# mainbd.net
KiCad netlist of a schematic drawn in EAGLE
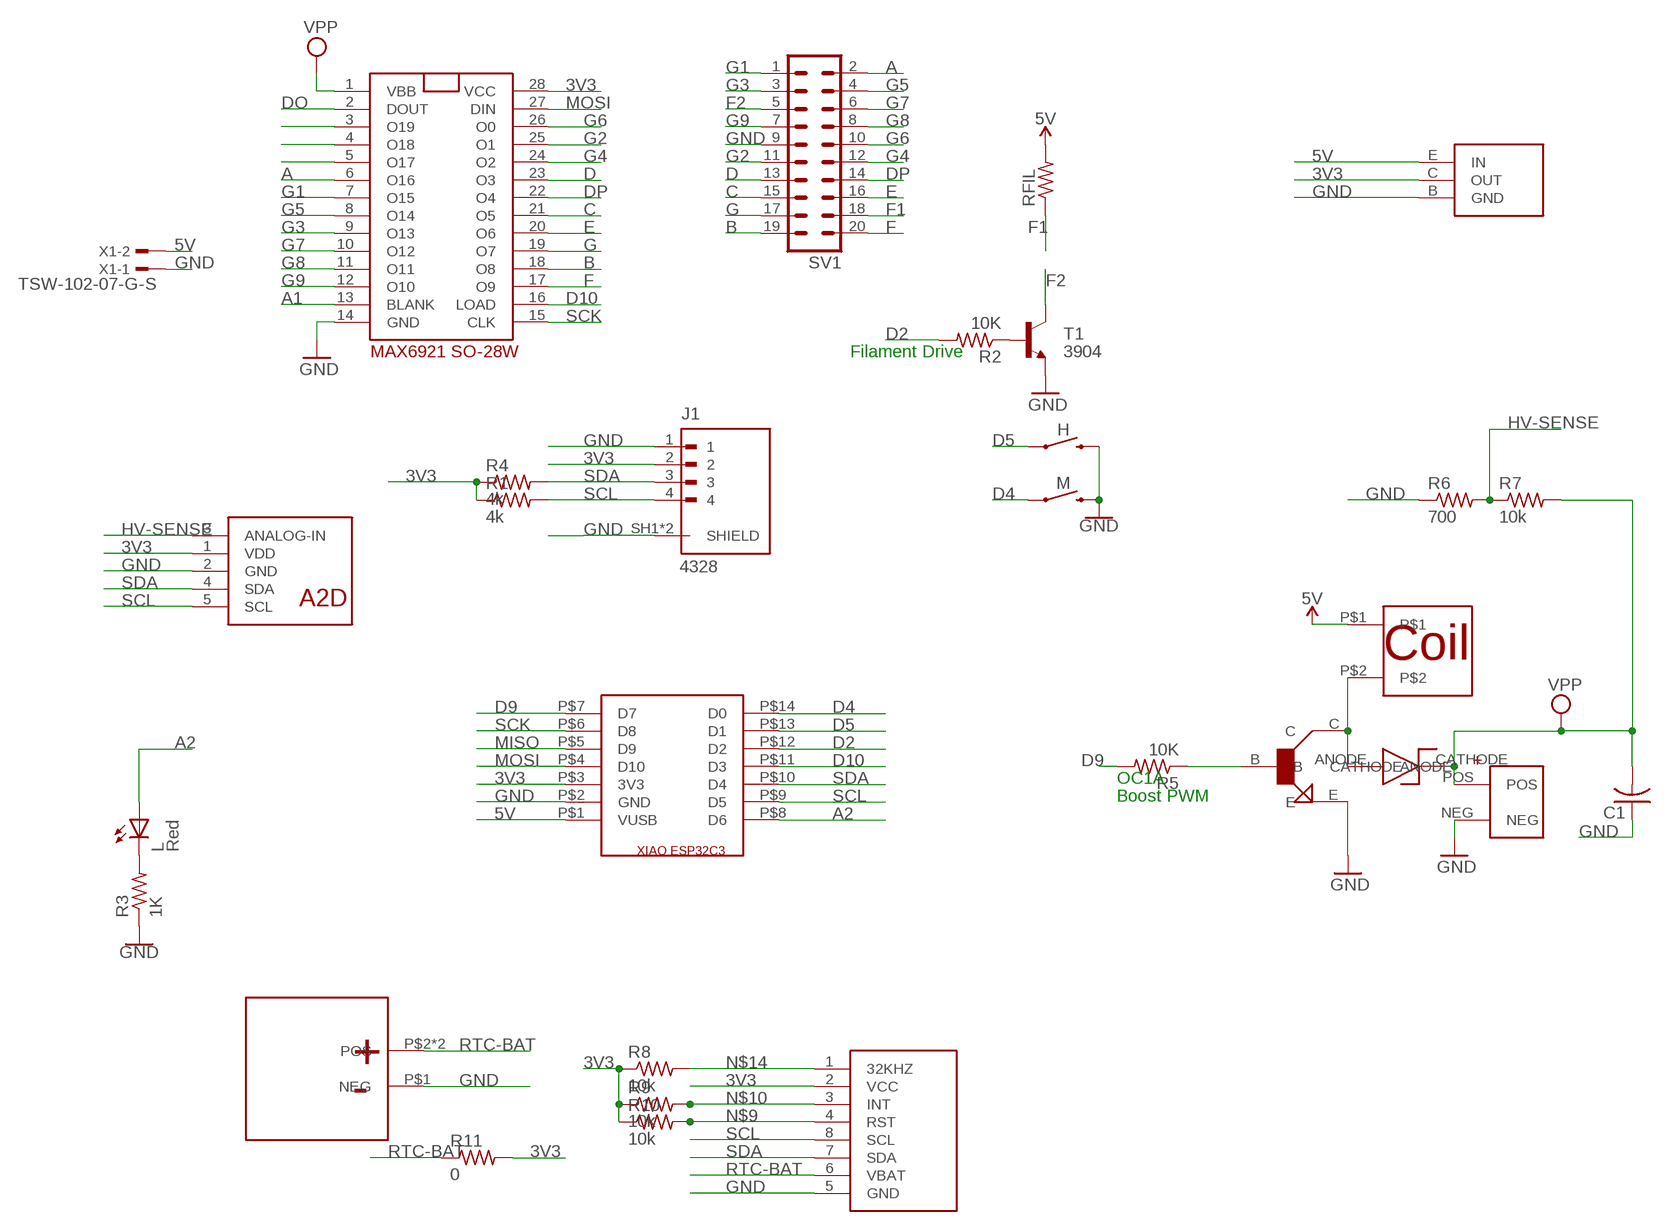
[diagram p0: schematic, sheet 1]

(export (version "E")
  (design (tool "Eeschema 10.0.6"))
  (components
    (comp (ref ".")
      (value "NPN-2SCR513P5")
      (footprint "eagle-import:SOT89-BCE")
      (libsource (lib "eagle-import") (part "NPN-2SCR513P5"))
    )
    (comp (ref "3.3V-LDO")
      (value "LDO-3.3V-AZ1117CR-3.3TRG1")
      (footprint "eagle-import:SOT89-BCE")
      (libsource (lib "eagle-import") (part "LDO-3.3V-AZ1117CR-3.3TRG1"))
    )
    (comp (ref "C1")
      (value "C-USC0805")
      (footprint "eagle-import:C0805")
      (libsource (lib "eagle-import") (part "C-USC0805"))
    )
    (comp (ref "H")
      (value "MOMENTARY-SWITCH-SPST-PTH-RIGHT-ANGLE-KIT")
      (footprint "eagle-import:TACTILE_SWITCH_PTH_RIGHT_ANGLE_KIT")
      (libsource (lib "eagle-import") (part "MOMENTARY-SWITCH-SPST-PTH-RIGHT-ANGLE-KIT"))
    )
    (comp (ref "J1")
      (value "4328")
      (footprint "eagle-import:ADAFRUIT_4328")
      (fields (field (name "MF") "Adafruit"))
      (libsource (lib "eagle-import") (part "4328"))
    )
    (comp (ref "L")
      (value "Red")
      (footprint "eagle-import:CHIP-LED0805")
      (libsource (lib "eagle-import") (part "LEDCHIP-LED0805"))
    )
    (comp (ref "M")
      (value "MOMENTARY-SWITCH-SPST-PTH-RIGHT-ANGLE-KIT")
      (footprint "eagle-import:TACTILE_SWITCH_PTH_RIGHT_ANGLE_KIT")
      (libsource (lib "eagle-import") (part "MOMENTARY-SWITCH-SPST-PTH-RIGHT-ANGLE-KIT"))
    )
    (comp (ref "R1")
      (value "4k")
      (footprint "eagle-import:R0805W")
      (libsource (lib "eagle-import") (part "rcl_334_R-US_R0805W"))
    )
    (comp (ref "R2")
      (value "10K")
      (footprint "eagle-import:M0805")
      (libsource (lib "eagle-import") (part "R-US_M0805"))
    )
    (comp (ref "R3")
      (value "1K")
      (footprint "eagle-import:M0805")
      (libsource (lib "eagle-import") (part "R-US_M0805"))
    )
    (comp (ref "R4")
      (value "4k")
      (footprint "eagle-import:R0805W")
      (libsource (lib "eagle-import") (part "rcl_334_R-US_R0805W"))
    )
    (comp (ref "R5")
      (value "10K")
      (footprint "eagle-import:M0805")
      (libsource (lib "eagle-import") (part "R-US_M0805"))
    )
    (comp (ref "R6")
      (value "700")
      (footprint "eagle-import:R0805W")
      (libsource (lib "eagle-import") (part "rcl_334_R-US_R0805W"))
    )
    (comp (ref "R7")
      (value "10k")
      (footprint "eagle-import:R0805W")
      (libsource (lib "eagle-import") (part "rcl_334_R-US_R0805W"))
    )
    (comp (ref "R8")
      (value "10k")
      (footprint "eagle-import:M0805")
      (libsource (lib "eagle-import") (part "rcl_334_R-US_M0805"))
    )
    (comp (ref "R9")
      (value "10k")
      (footprint "eagle-import:M0805")
      (libsource (lib "eagle-import") (part "rcl_334_R-US_M0805"))
    )
    (comp (ref "R10")
      (value "10k")
      (footprint "eagle-import:M0805")
      (libsource (lib "eagle-import") (part "rcl_334_R-US_M0805"))
    )
    (comp (ref "R11")
      (value "0")
      (footprint "eagle-import:M0805")
      (libsource (lib "eagle-import") (part "rcl_334_R-US_M0805"))
    )
    (comp (ref "RFIL")
      (value "FLIPFLOP-RES")
      (footprint "eagle-import:0805-THM")
      (libsource (lib "eagle-import") (part "FLIPFLOP-RES"))
    )
    (comp (ref "SV1")
      (value "MA10-2")
      (footprint "eagle-import:MA10-2")
      (libsource (lib "eagle-import") (part "MA10-2"))
    )
    (comp (ref "T1")
      (value "3904")
      (footprint "eagle-import:SOT23-BEC")
      (libsource (lib "eagle-import") (part "-NPN-SOT23-BECMMBT3904LT1"))
    )
    (comp (ref "U$1")
      (value "MAX6921")
      (footprint "eagle-import:SO28W")
      (libsource (lib "eagle-import") (part "MAX6921"))
    )
    (comp (ref "U$3")
      (value "DS3231M")
      (footprint "eagle-import:SOIC8")
      (libsource (lib "eagle-import") (part "DS3231M"))
    )
    (comp (ref "U$4")
      (value "CAP-330")
      (footprint "eagle-import:CAP-330")
      (libsource (lib "eagle-import") (part "CAP-330"))
    )
    (comp (ref "U$5")
      (value "BATTERY-2998-COIN")
      (footprint "eagle-import:BATTERY-2998-COIN")
      (libsource (lib "eagle-import") (part "BATTERY-2998-COIN"))
    )
    (comp (ref "U$6")
      (value "INDUCTOR-453226")
      (footprint "eagle-import:INDUCTOR-453226")
      (libsource (lib "eagle-import") (part "INDUCTOR-453226"))
    )
    (comp (ref "U$7")
      (value "XIAOESP32C3")
      (footprint "eagle-import:XIAOESP32C3")
      (libsource (lib "eagle-import") (part "XIAOESP32C3"))
    )
    (comp (ref "U$8")
      (value "A2D-MCP3221A6T")
      (footprint "eagle-import:SOT23-5")
      (libsource (lib "eagle-import") (part "A2D-MCP3221A6T"))
    )
    (comp (ref "U$9")
      (value "DIODE-ZENIER-CMSH1-20MLTR13")
      (footprint "eagle-import:SMA-DIODE")
      (libsource (lib "eagle-import") (part "DIODE-ZENIER-CMSH1-20MLTR13"))
    )
    (comp (ref "X1")
      (value "TSW-102-07-G-S")
      (footprint "eagle-import:TSW-102-XX-G-S")
      (fields (field (name "MF") "Samtec Inc."))
      (libsource (lib "eagle-import") (part "TSW-102--G-S07"))
    )
  )
  (nets
    (net (code "1") (name "/3V3") (class "Default")
      (node (ref "3.3V-LDO") (pin "C") (pinfunction "OUT_C") (pintype "bidirectional"))
      (node (ref "J1") (pin "2") (pinfunction "2_2") (pintype "passive"))
      (node (ref "R1") (pin "1") (pinfunction "1_1") (pintype "passive"))
      (node (ref "R10") (pin "1") (pinfunction "1_1") (pintype "passive"))
      (node (ref "R11") (pin "2") (pinfunction "2_2") (pintype "passive"))
      (node (ref "R4") (pin "1") (pinfunction "1_1") (pintype "passive"))
      (node (ref "R8") (pin "1") (pinfunction "1_1") (pintype "passive"))
      (node (ref "R9") (pin "1") (pinfunction "1_1") (pintype "passive"))
      (node (ref "U$1") (pin "28") (pinfunction "VCC_28") (pintype "bidirectional"))
      (node (ref "U$3") (pin "2") (pinfunction "VCC_2") (pintype "bidirectional"))
      (node (ref "U$7") (pin "P$3") (pinfunction "3V3_P$3") (pintype "bidirectional"))
      (node (ref "U$8") (pin "1") (pinfunction "VDD_1") (pintype "bidirectional"))
    )
    (net (code "2") (name "/A") (class "Default")
      (node (ref "SV1") (pin "2") (pinfunction "2_2") (pintype "passive"))
      (node (ref "U$1") (pin "6") (pinfunction "O16_6") (pintype "bidirectional"))
    )
    (net (code "3") (name "/A1") (class "Default")
      (node (ref "U$1") (pin "13") (pinfunction "BLANK_13") (pintype "bidirectional"))
    )
    (net (code "4") (name "/A2") (class "Default")
      (node (ref "L") (pin "A") (pinfunction "A_A") (pintype "passive"))
      (node (ref "U$7") (pin "P$8") (pinfunction "D6_P$8") (pintype "bidirectional"))
    )
    (net (code "5") (name "/B") (class "Default")
      (node (ref "SV1") (pin "19") (pinfunction "19_19") (pintype "passive"))
      (node (ref "U$1") (pin "18") (pinfunction "O8_18") (pintype "bidirectional"))
    )
    (net (code "6") (name "/C") (class "Default")
      (node (ref "SV1") (pin "15") (pinfunction "15_15") (pintype "passive"))
      (node (ref "U$1") (pin "21") (pinfunction "O5_21") (pintype "bidirectional"))
    )
    (net (code "7") (name "/D") (class "Default")
      (node (ref "SV1") (pin "13") (pinfunction "13_13") (pintype "passive"))
      (node (ref "U$1") (pin "23") (pinfunction "O3_23") (pintype "bidirectional"))
    )
    (net (code "8") (name "/D2") (class "Default")
      (node (ref "R2") (pin "2") (pinfunction "2_2") (pintype "passive"))
      (node (ref "U$7") (pin "P$12") (pinfunction "D2_P$12") (pintype "bidirectional"))
    )
    (net (code "9") (name "/D4") (class "Default")
      (node (ref "M") (pin "1") (pinfunction "1_1") (pintype "passive"))
      (node (ref "U$7") (pin "P$14") (pinfunction "D0_P$14") (pintype "bidirectional"))
    )
    (net (code "10") (name "/D5") (class "Default")
      (node (ref "H") (pin "1") (pinfunction "1_1") (pintype "passive"))
      (node (ref "U$7") (pin "P$13") (pinfunction "D1_P$13") (pintype "bidirectional"))
    )
    (net (code "11") (name "/D9") (class "Default")
      (node (ref "R5") (pin "2") (pinfunction "2_2") (pintype "passive"))
      (node (ref "U$7") (pin "P$7") (pinfunction "D7_P$7") (pintype "bidirectional"))
    )
    (net (code "12") (name "/D10") (class "Default")
      (node (ref "U$1") (pin "16") (pinfunction "LOAD_16") (pintype "bidirectional"))
      (node (ref "U$7") (pin "P$11") (pinfunction "D3_P$11") (pintype "bidirectional"))
    )
    (net (code "13") (name "/DO") (class "Default")
      (node (ref "U$1") (pin "2") (pinfunction "DOUT_2") (pintype "bidirectional"))
    )
    (net (code "14") (name "/DP") (class "Default")
      (node (ref "SV1") (pin "14") (pinfunction "14_14") (pintype "passive"))
      (node (ref "U$1") (pin "22") (pinfunction "O4_22") (pintype "bidirectional"))
    )
    (net (code "15") (name "/E") (class "Default")
      (node (ref "SV1") (pin "16") (pinfunction "16_16") (pintype "passive"))
      (node (ref "U$1") (pin "20") (pinfunction "O6_20") (pintype "bidirectional"))
    )
    (net (code "16") (name "/F") (class "Default")
      (node (ref "SV1") (pin "20") (pinfunction "20_20") (pintype "passive"))
      (node (ref "U$1") (pin "17") (pinfunction "O9_17") (pintype "bidirectional"))
    )
    (net (code "17") (name "/F1") (class "Default")
      (node (ref "RFIL") (pin "1") (pinfunction "1_1") (pintype "passive"))
      (node (ref "SV1") (pin "18") (pinfunction "18_18") (pintype "passive"))
    )
    (net (code "18") (name "/F2") (class "Default")
      (node (ref "SV1") (pin "5") (pinfunction "5_5") (pintype "passive"))
      (node (ref "T1") (pin "C") (pinfunction "C_C") (pintype "passive"))
    )
    (net (code "19") (name "/G") (class "Default")
      (node (ref "SV1") (pin "17") (pinfunction "17_17") (pintype "passive"))
      (node (ref "U$1") (pin "19") (pinfunction "O7_19") (pintype "bidirectional"))
    )
    (net (code "20") (name "/G1") (class "Default")
      (node (ref "SV1") (pin "1") (pinfunction "1_1") (pintype "passive"))
      (node (ref "U$1") (pin "7") (pinfunction "O15_7") (pintype "bidirectional"))
    )
    (net (code "21") (name "/G2") (class "Default")
      (node (ref "SV1") (pin "11") (pinfunction "11_11") (pintype "passive"))
      (node (ref "U$1") (pin "25") (pinfunction "O1_25") (pintype "bidirectional"))
    )
    (net (code "22") (name "/G3") (class "Default")
      (node (ref "SV1") (pin "3") (pinfunction "3_3") (pintype "passive"))
      (node (ref "U$1") (pin "9") (pinfunction "O13_9") (pintype "bidirectional"))
    )
    (net (code "23") (name "/G4") (class "Default")
      (node (ref "SV1") (pin "12") (pinfunction "12_12") (pintype "passive"))
      (node (ref "U$1") (pin "24") (pinfunction "O2_24") (pintype "bidirectional"))
    )
    (net (code "24") (name "/G5") (class "Default")
      (node (ref "SV1") (pin "4") (pinfunction "4_4") (pintype "passive"))
      (node (ref "U$1") (pin "8") (pinfunction "O14_8") (pintype "bidirectional"))
    )
    (net (code "25") (name "/G6") (class "Default")
      (node (ref "SV1") (pin "10") (pinfunction "10_10") (pintype "passive"))
      (node (ref "U$1") (pin "26") (pinfunction "O0_26") (pintype "bidirectional"))
    )
    (net (code "26") (name "/G7") (class "Default")
      (node (ref "SV1") (pin "6") (pinfunction "6_6") (pintype "passive"))
      (node (ref "U$1") (pin "10") (pinfunction "O12_10") (pintype "bidirectional"))
    )
    (net (code "27") (name "/G8") (class "Default")
      (node (ref "SV1") (pin "8") (pinfunction "8_8") (pintype "passive"))
      (node (ref "U$1") (pin "11") (pinfunction "O11_11") (pintype "bidirectional"))
    )
    (net (code "28") (name "/G9") (class "Default")
      (node (ref "SV1") (pin "7") (pinfunction "7_7") (pintype "passive"))
      (node (ref "U$1") (pin "12") (pinfunction "O10_12") (pintype "bidirectional"))
    )
    (net (code "29") (name "/HV-SENSE") (class "Default")
      (node (ref "R6") (pin "2") (pinfunction "2_2") (pintype "passive"))
      (node (ref "R7") (pin "1") (pinfunction "1_1") (pintype "passive"))
      (node (ref "U$8") (pin "3") (pinfunction "ANALOG-IN_3") (pintype "bidirectional"))
    )
    (net (code "30") (name "/MISO") (class "Default")
      (node (ref "U$7") (pin "P$5") (pinfunction "D9_P$5") (pintype "bidirectional"))
    )
    (net (code "31") (name "/MOSI") (class "Default")
      (node (ref "U$1") (pin "27") (pinfunction "DIN_27") (pintype "bidirectional"))
      (node (ref "U$7") (pin "P$4") (pinfunction "D10_P$4") (pintype "bidirectional"))
    )
    (net (code "32") (name "/N$9") (class "Default")
      (node (ref "R10") (pin "2") (pinfunction "2_2") (pintype "passive"))
      (node (ref "U$3") (pin "4") (pinfunction "RST_4") (pintype "bidirectional"))
    )
    (net (code "33") (name "/N$10") (class "Default")
      (node (ref "R9") (pin "2") (pinfunction "2_2") (pintype "passive"))
      (node (ref "U$3") (pin "3") (pinfunction "INT_3") (pintype "bidirectional"))
    )
    (net (code "34") (name "/N$14") (class "Default")
      (node (ref "R8") (pin "2") (pinfunction "2_2") (pintype "passive"))
      (node (ref "U$3") (pin "1") (pinfunction "32KHZ_1") (pintype "bidirectional"))
    )
    (net (code "35") (name "/RTC-BAT") (class "Default")
      (node (ref "R11") (pin "1") (pinfunction "1_1") (pintype "passive"))
      (node (ref "U$3") (pin "6") (pinfunction "VBAT_6") (pintype "bidirectional"))
      (node (ref "U$5") (pin "P$2") (pinfunction "POS_P$2") (pintype "bidirectional"))
      (node (ref "U$5") (pin "P$3") (pinfunction "POS_P$3") (pintype "bidirectional"))
    )
    (net (code "36") (name "/SCK") (class "Default")
      (node (ref "U$1") (pin "15") (pinfunction "CLK_15") (pintype "bidirectional"))
      (node (ref "U$7") (pin "P$6") (pinfunction "D8_P$6") (pintype "bidirectional"))
    )
    (net (code "37") (name "/SCL") (class "Default")
      (node (ref "J1") (pin "4") (pinfunction "4_4") (pintype "passive"))
      (node (ref "R1") (pin "2") (pinfunction "2_2") (pintype "passive"))
      (node (ref "U$3") (pin "8") (pinfunction "SCL_8") (pintype "bidirectional"))
      (node (ref "U$7") (pin "P$9") (pinfunction "D5_P$9") (pintype "bidirectional"))
      (node (ref "U$8") (pin "5") (pinfunction "SCL_5") (pintype "bidirectional"))
    )
    (net (code "38") (name "/SDA") (class "Default")
      (node (ref "J1") (pin "3") (pinfunction "3_3") (pintype "passive"))
      (node (ref "R4") (pin "2") (pinfunction "2_2") (pintype "passive"))
      (node (ref "U$3") (pin "7") (pinfunction "SDA_7") (pintype "bidirectional"))
      (node (ref "U$7") (pin "P$10") (pinfunction "D4_P$10") (pintype "bidirectional"))
      (node (ref "U$8") (pin "4") (pinfunction "SDA_4") (pintype "bidirectional"))
    )
    (net (code "39") (name "5V") (class "Default")
      (node (ref "3.3V-LDO") (pin "E") (pinfunction "IN_E") (pintype "bidirectional"))
      (node (ref "RFIL") (pin "2") (pinfunction "2_2") (pintype "passive"))
      (node (ref "U$6") (pin "P$1") (pinfunction "P$1_P$1") (pintype "bidirectional"))
      (node (ref "U$7") (pin "P$1") (pinfunction "VUSB_P$1") (pintype "bidirectional"))
      (node (ref "X1") (pin "2") (pinfunction "1_2") (pintype "passive"))
    )
    (net (code "40") (name "GND") (class "Default")
      (node (ref ".") (pin "E") (pinfunction "E_E") (pintype "bidirectional"))
      (node (ref "3.3V-LDO") (pin "B") (pinfunction "GND_B") (pintype "bidirectional"))
      (node (ref "C1") (pin "1") (pinfunction "1_1") (pintype "passive"))
      (node (ref "H") (pin "2") (pinfunction "2_2") (pintype "passive"))
      (node (ref "J1") (pin "1") (pinfunction "1_1") (pintype "passive"))
      (node (ref "J1") (pin "SH1") (pinfunction "SHIELD_SH1") (pintype "passive"))
      (node (ref "J1") (pin "SH2") (pinfunction "SHIELD_SH2") (pintype "passive"))
      (node (ref "M") (pin "2") (pinfunction "2_2") (pintype "passive"))
      (node (ref "R3") (pin "1") (pinfunction "1_1") (pintype "passive"))
      (node (ref "R6") (pin "1") (pinfunction "1_1") (pintype "passive"))
      (node (ref "SV1") (pin "9") (pinfunction "9_9") (pintype "passive"))
      (node (ref "T1") (pin "E") (pinfunction "E_E") (pintype "passive"))
      (node (ref "U$1") (pin "14") (pinfunction "GND_14") (pintype "bidirectional"))
      (node (ref "U$3") (pin "5") (pinfunction "GND_5") (pintype "bidirectional"))
      (node (ref "U$4") (pin "NEG") (pinfunction "NEG_NEG") (pintype "bidirectional"))
      (node (ref "U$5") (pin "P$1") (pinfunction "NEG_P$1") (pintype "bidirectional"))
      (node (ref "U$7") (pin "P$2") (pinfunction "GND_P$2") (pintype "bidirectional"))
      (node (ref "U$8") (pin "2") (pinfunction "GND_2") (pintype "bidirectional"))
      (node (ref "X1") (pin "1") (pinfunction "1_1") (pintype "passive"))
    )
    (net (code "41") (name "Net-(.-PadB)") (class "Default")
      (node (ref ".") (pin "B") (pinfunction "B_B") (pintype "bidirectional"))
      (node (ref "R5") (pin "1") (pinfunction "1_1") (pintype "passive"))
    )
    (net (code "42") (name "Net-(.-PadC)") (class "Default")
      (node (ref ".") (pin "C") (pinfunction "C_C") (pintype "bidirectional"))
      (node (ref "U$6") (pin "P$2") (pinfunction "P$2_P$2") (pintype "bidirectional"))
      (node (ref "U$9") (pin "ANODE") (pinfunction "ANODE_ANODE") (pintype "bidirectional"))
    )
    (net (code "43") (name "Net-(L-PadC)") (class "Default")
      (node (ref "L") (pin "C") (pinfunction "C_C") (pintype "passive"))
      (node (ref "R3") (pin "2") (pinfunction "2_2") (pintype "passive"))
    )
    (net (code "44") (name "Net-(R2-Pad1)") (class "Default")
      (node (ref "R2") (pin "1") (pinfunction "1_1") (pintype "passive"))
      (node (ref "T1") (pin "B") (pinfunction "B_B") (pintype "passive"))
    )
    (net (code "45") (name "VPP") (class "Default")
      (node (ref "C1") (pin "2") (pinfunction "2_2") (pintype "passive"))
      (node (ref "R7") (pin "2") (pinfunction "2_2") (pintype "passive"))
      (node (ref "U$1") (pin "1") (pinfunction "VBB_1") (pintype "bidirectional"))
      (node (ref "U$4") (pin "POS") (pinfunction "POS_POS") (pintype "bidirectional"))
      (node (ref "U$9") (pin "CATHODE") (pinfunction "CATHODE_CATHODE") (pintype "bidirectional"))
    )
    (net (code "46") (name "unconnected-(U$1-O17-Pad5)") (class "Default")
      (node (ref "U$1") (pin "5") (pinfunction "O17_5") (pintype "bidirectional"))
    )
    (net (code "47") (name "unconnected-(U$1-O18-Pad4)") (class "Default")
      (node (ref "U$1") (pin "4") (pinfunction "O18_4") (pintype "bidirectional"))
    )
    (net (code "48") (name "unconnected-(U$1-O19-Pad3)") (class "Default")
      (node (ref "U$1") (pin "3") (pinfunction "O19_3") (pintype "bidirectional"))
    )
  )
)
